# InkTime.net
KiCad netlist of a schematic drawn in EAGLE
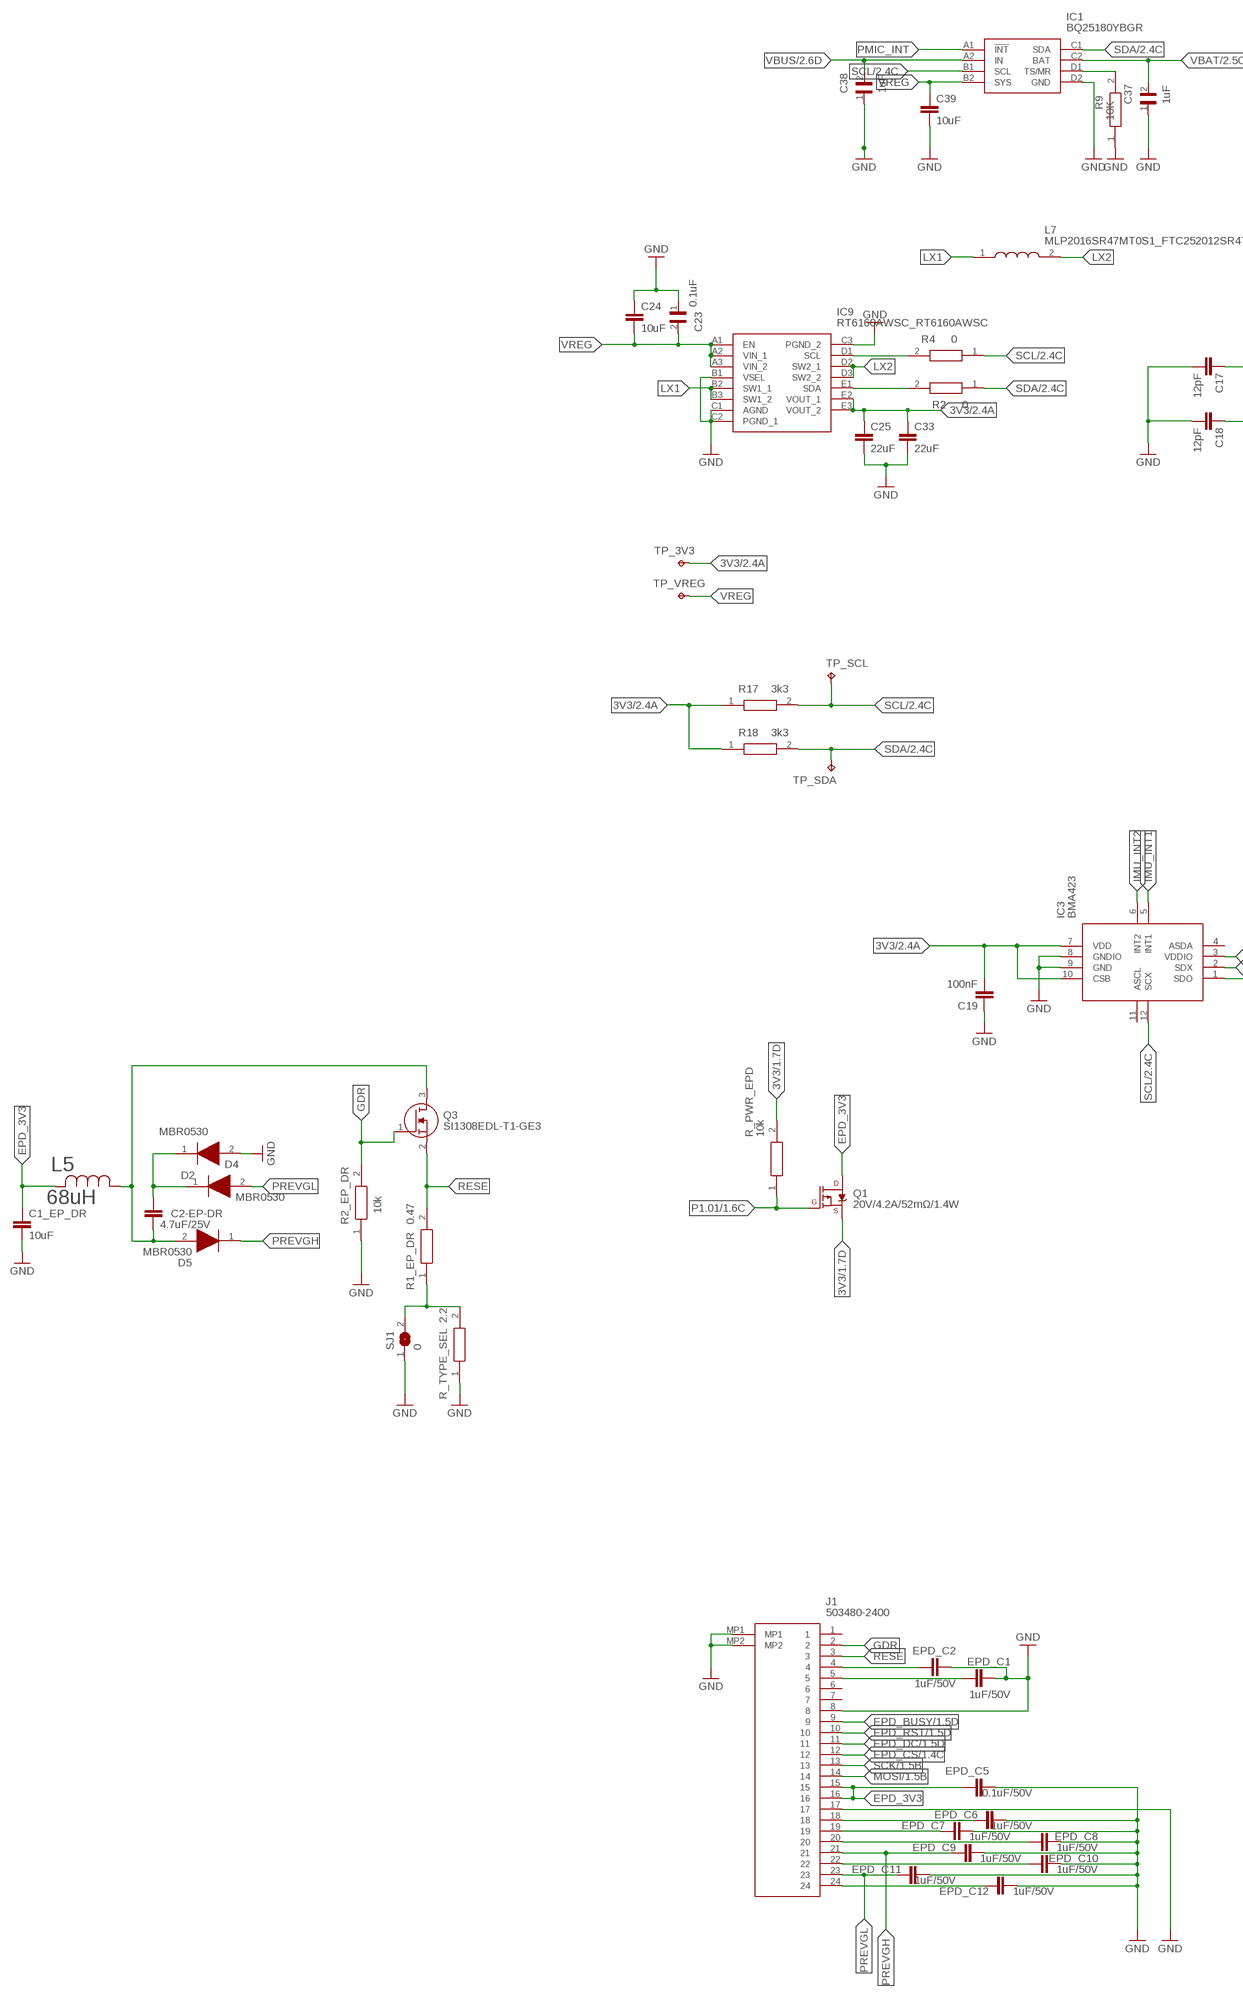
[diagram p0: schematic, sheet 1, part 1 of 2]
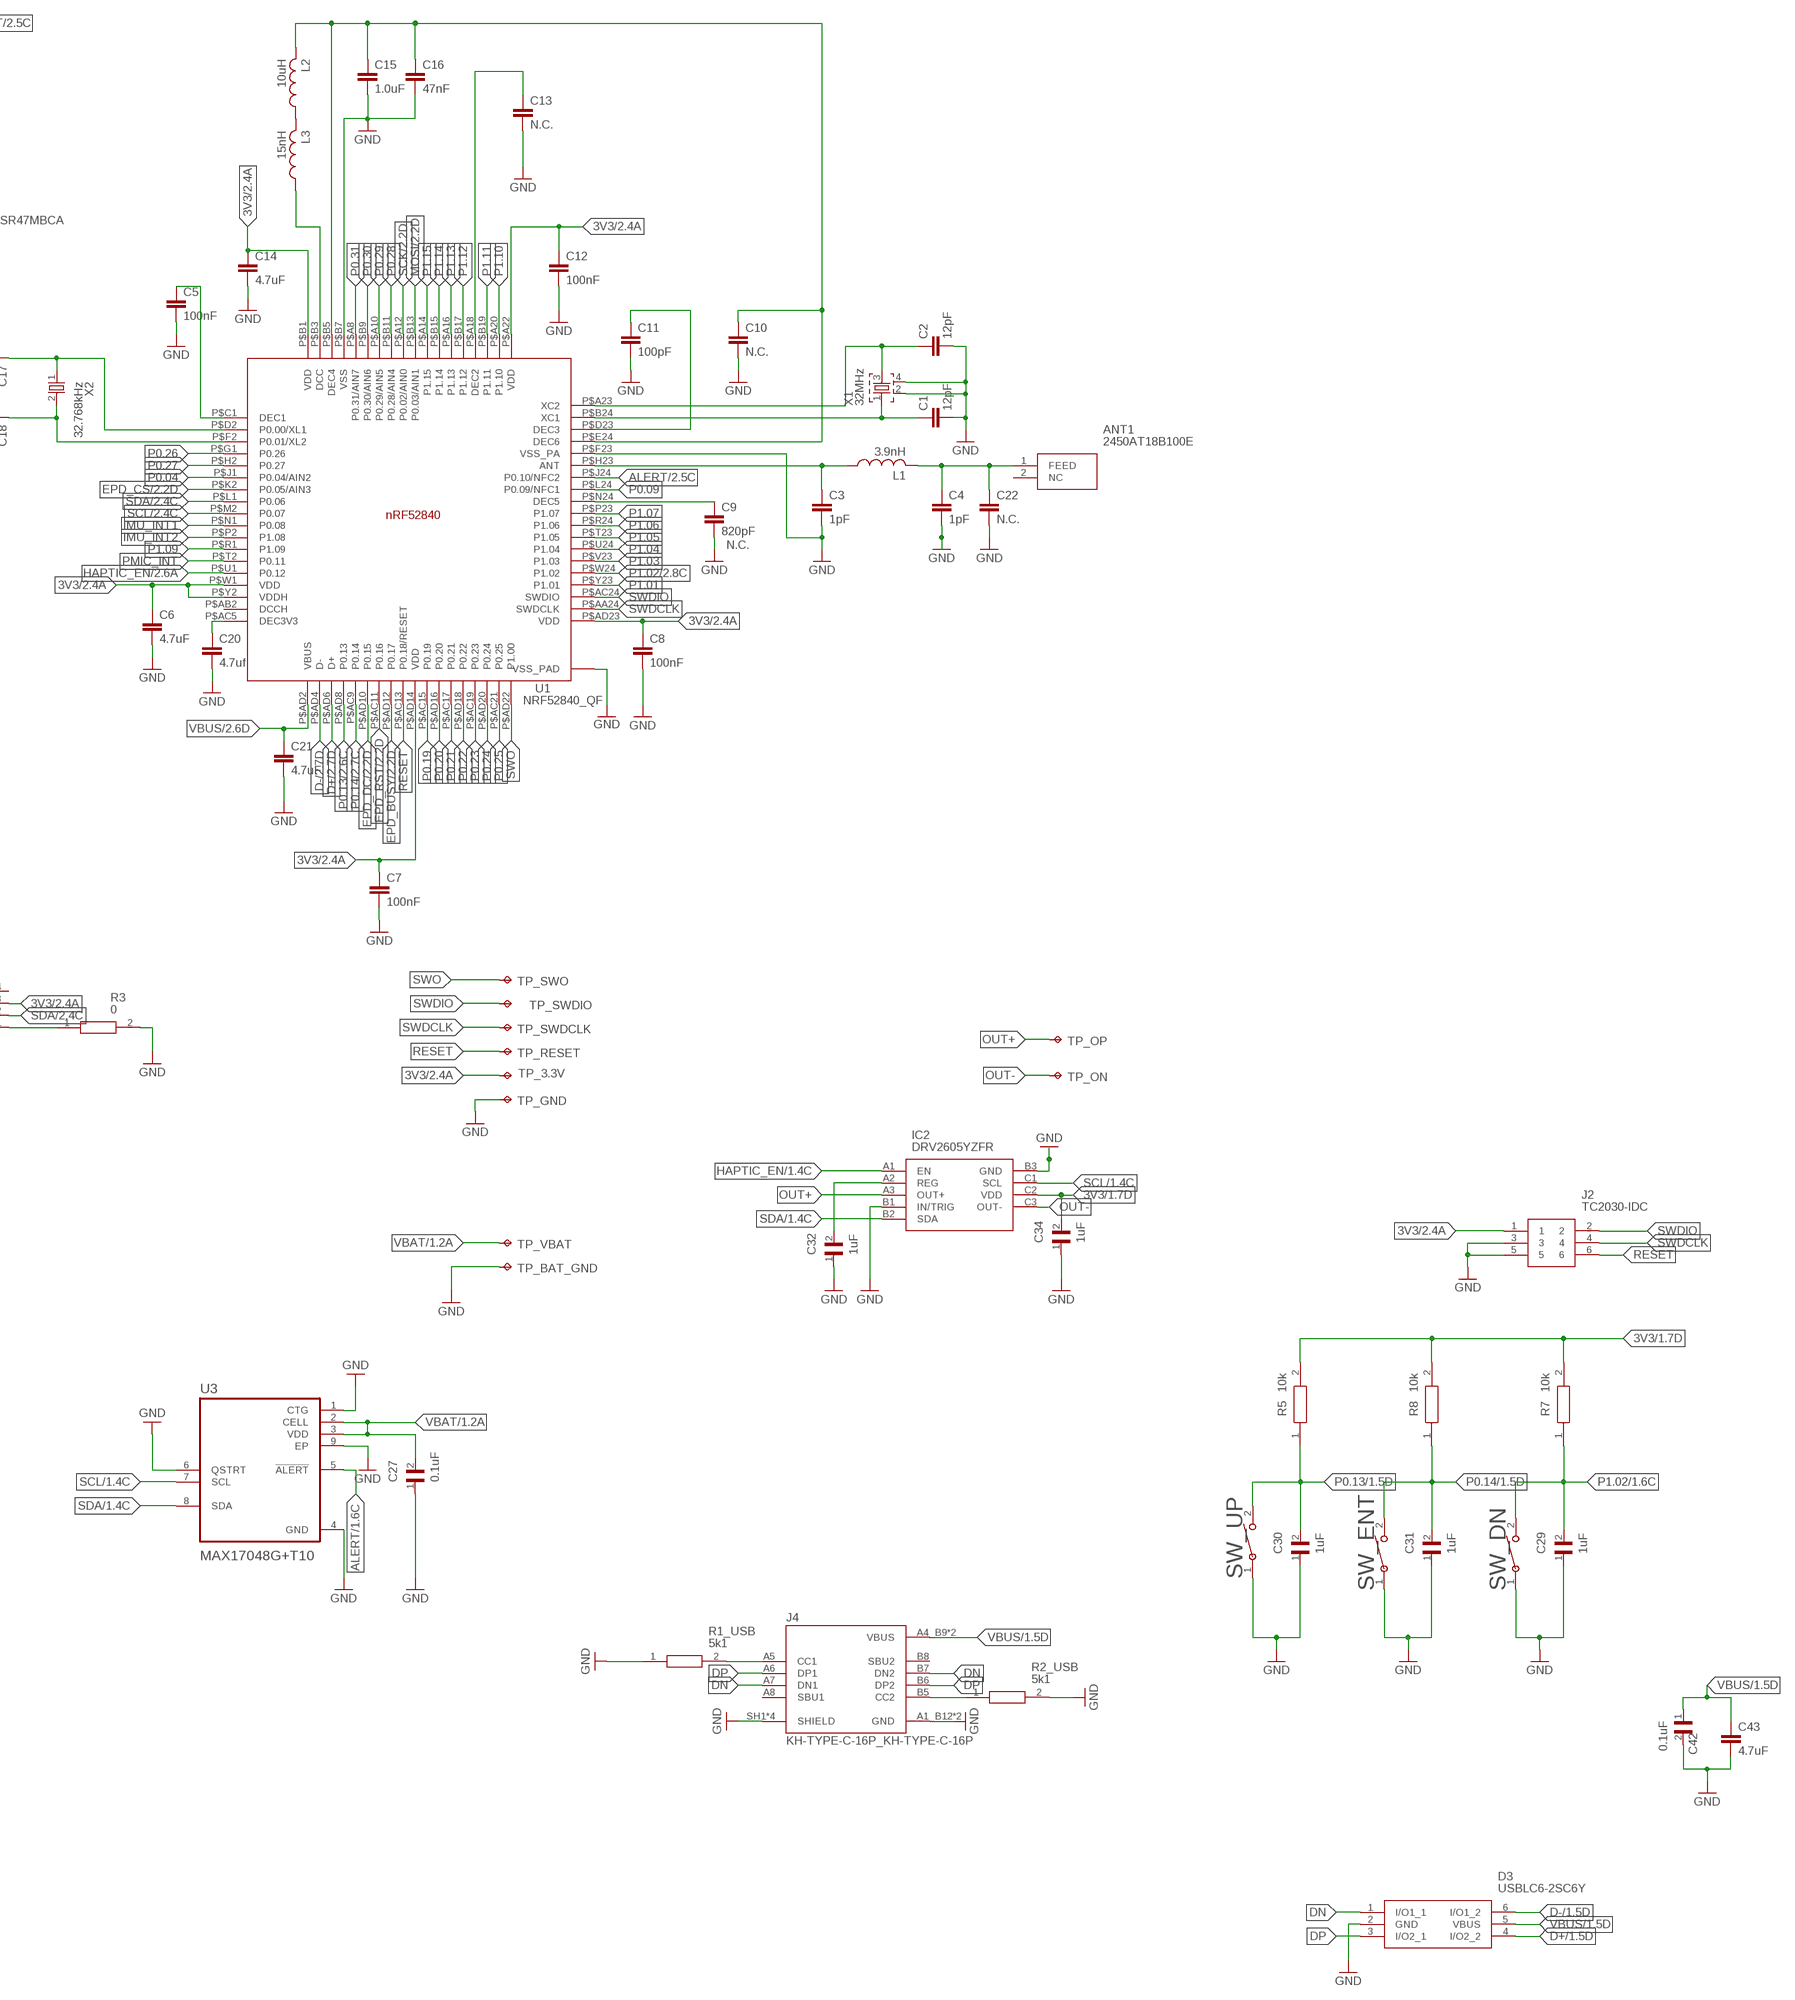
[diagram p1: schematic, sheet 1, part 2 of 2]

(export (version "E")
  (design (tool "Eeschema 10.0.6"))
  (components
    (comp (ref "ANT1")
      (value "2450AT18B100E")
      (footprint "eagle-import:2450AT18B100E_ANTC3216X140N")
      (fields (field (name "MOUSER_PART_NUMBER") "609-2450AT18B100E"))
      (libsource (lib "eagle-import") (part "2450AT18B100E_2450AT18B100E"))
    )
    (comp (ref "C1")
      (value "12pF")
      (footprint "eagle-import:NORDIC_NRF_3_RESC0201_L")
      (libsource (lib "eagle-import") (part "NORDIC_NRF_3_CAPACITOR_0201_L"))
    )
    (comp (ref "C1_EP_DR")
      (value "10uF")
      (footprint "eagle-import:NORDIC_NRF_3_RESC0402_L")
      (libsource (lib "eagle-import") (part "NORDIC_NRF_3_CAPACITOR_0402_L"))
    )
    (comp (ref "C2")
      (value "12pF")
      (footprint "eagle-import:NORDIC_NRF_3_RESC0201_L")
      (libsource (lib "eagle-import") (part "NORDIC_NRF_3_CAPACITOR_0201_L"))
    )
    (comp (ref "C2-EP-DR")
      (value "4.7uF/25V")
      (footprint "eagle-import:NORDIC_NRF_3_RESC0603_L")
      (libsource (lib "eagle-import") (part "NORDIC_NRF_3_CAPACITOR_0603_L"))
    )
    (comp (ref "C3")
      (value "1pF")
      (footprint "eagle-import:NORDIC_NRF_3_RESC0201_L")
      (libsource (lib "eagle-import") (part "NORDIC_NRF_3_CAPACITOR_0201_L"))
    )
    (comp (ref "C4")
      (value "1pF")
      (footprint "eagle-import:NORDIC_NRF_3_RESC0201_L")
      (libsource (lib "eagle-import") (part "NORDIC_NRF_3_CAPACITOR_0201_L"))
    )
    (comp (ref "C5")
      (value "100nF")
      (footprint "eagle-import:NORDIC_NRF_3_RESC0201_L")
      (libsource (lib "eagle-import") (part "NORDIC_NRF_3_CAPACITOR_0201_L"))
    )
    (comp (ref "C6")
      (value "4.7uF")
      (footprint "eagle-import:NORDIC_NRF_3_RESC0402_L")
      (libsource (lib "eagle-import") (part "NORDIC_NRF_3_CAPACITOR_0402_L"))
    )
    (comp (ref "C7")
      (value "100nF")
      (footprint "eagle-import:NORDIC_NRF_3_RESC0201_L")
      (libsource (lib "eagle-import") (part "NORDIC_NRF_3_CAPACITOR_0201_L"))
    )
    (comp (ref "C8")
      (value "100nF")
      (footprint "eagle-import:NORDIC_NRF_3_RESC0201_L")
      (libsource (lib "eagle-import") (part "NORDIC_NRF_3_CAPACITOR_0201_L"))
    )
    (comp (ref "C9")
      (value "820pF")
      (footprint "eagle-import:NORDIC_NRF_3_RESC0201_L")
      (fields (field (name "STATUS") "N.C."))
      (libsource (lib "eagle-import") (part "NORDIC_NRF_3_CAPACITOR_0201_L"))
    )
    (comp (ref "C10")
      (value "N.C.")
      (footprint "eagle-import:NORDIC_NRF_3_RESC0402_L")
      (libsource (lib "eagle-import") (part "NORDIC_NRF_3_CAPACITOR_0402_L"))
    )
    (comp (ref "C11")
      (value "100pF")
      (footprint "eagle-import:NORDIC_NRF_3_RESC0201_L")
      (libsource (lib "eagle-import") (part "NORDIC_NRF_3_CAPACITOR_0201_L"))
    )
    (comp (ref "C12")
      (value "100nF")
      (footprint "eagle-import:NORDIC_NRF_3_RESC0201_L")
      (libsource (lib "eagle-import") (part "NORDIC_NRF_3_CAPACITOR_0201_L"))
    )
    (comp (ref "C13")
      (value "N.C.")
      (footprint "eagle-import:NORDIC_NRF_3_RESC0402_L")
      (libsource (lib "eagle-import") (part "NORDIC_NRF_3_CAPACITOR_0402_L"))
    )
    (comp (ref "C14")
      (value "4.7uF")
      (footprint "eagle-import:NORDIC_NRF_3_RESC0402_L")
      (libsource (lib "eagle-import") (part "NORDIC_NRF_3_CAPACITOR_0402_L"))
    )
    (comp (ref "C15")
      (value "1.0uF")
      (footprint "eagle-import:NORDIC_NRF_3_RESC0402_L")
      (libsource (lib "eagle-import") (part "NORDIC_NRF_3_CAPACITOR_0402_L"))
    )
    (comp (ref "C16")
      (value "47nF")
      (footprint "eagle-import:NORDIC_NRF_3_RESC0201_L")
      (libsource (lib "eagle-import") (part "NORDIC_NRF_3_CAPACITOR_0201_L"))
    )
    (comp (ref "C17")
      (value "12pF")
      (footprint "eagle-import:NORDIC_NRF_3_RESC0201_L")
      (libsource (lib "eagle-import") (part "NORDIC_NRF_3_CAPACITOR_0201_L"))
    )
    (comp (ref "C18")
      (value "12pF")
      (footprint "eagle-import:NORDIC_NRF_3_RESC0201_L")
      (libsource (lib "eagle-import") (part "NORDIC_NRF_3_CAPACITOR_0201_L"))
    )
    (comp (ref "C19")
      (value "100nF")
      (footprint "eagle-import:NORDIC_NRF_3_RESC0201_L")
      (libsource (lib "eagle-import") (part "NORDIC_NRF_3_CAPACITOR_0201_L"))
    )
    (comp (ref "C20")
      (value "4.7uf")
      (footprint "eagle-import:NORDIC_NRF_3_RESC0201_L")
      (libsource (lib "eagle-import") (part "NORDIC_NRF_3_CAPACITOR_0201_L"))
    )
    (comp (ref "C21")
      (value "4.7uF")
      (footprint "eagle-import:NORDIC_NRF_3_RESC0402_L")
      (libsource (lib "eagle-import") (part "NORDIC_NRF_3_CAPACITOR_0402_L"))
    )
    (comp (ref "C22")
      (value "N.C.")
      (footprint "eagle-import:NORDIC_NRF_3_RESC0402_L")
      (libsource (lib "eagle-import") (part "NORDIC_NRF_3_CAPACITOR_0402_L"))
    )
    (comp (ref "C23")
      (value "0.1uF")
      (footprint "eagle-import:GRM011R60J152KE01L_2_CAPC0201X13N")
      (fields (field (name "MF") "Murata") (field (name "MP") "GRM011R60J152KE01L"))
      (libsource (lib "eagle-import") (part "GRM011R60J152KE01L_2_GRM011R60J152KE01L"))
    )
    (comp (ref "C24")
      (value "10uF")
      (footprint "eagle-import:NORDIC_NRF_3_RESC0402_L")
      (libsource (lib "eagle-import") (part "NORDIC_NRF_3_CAPACITOR_0402_L"))
    )
    (comp (ref "C25")
      (value "22uF")
      (footprint "eagle-import:NORDIC_NRF_3_RESC0402_L")
      (libsource (lib "eagle-import") (part "NORDIC_NRF_3_CAPACITOR_0402_L"))
    )
    (comp (ref "C27")
      (value "0.1uF")
      (footprint "eagle-import:GRM011R60J152KE01L_2_CAPC0201X13N")
      (fields (field (name "MF") "Murata") (field (name "MP") "GRM011R60J152KE01L"))
      (libsource (lib "eagle-import") (part "GRM011R60J152KE01L_2_GRM011R60J152KE01L"))
    )
    (comp (ref "C29")
      (value "1uF")
      (footprint "eagle-import:GRM011R60J152KE01L_2_CAPC0201X13N")
      (fields (field (name "MF") "Murata") (field (name "MP") "GRM011R60J152KE01L"))
      (libsource (lib "eagle-import") (part "GRM011R60J152KE01L_2_GRM011R60J152KE01L"))
    )
    (comp (ref "C30")
      (value "1uF")
      (footprint "eagle-import:GRM011R60J152KE01L_2_CAPC0201X13N")
      (fields (field (name "MF") "Murata") (field (name "MP") "GRM011R60J152KE01L"))
      (libsource (lib "eagle-import") (part "GRM011R60J152KE01L_2_GRM011R60J152KE01L"))
    )
    (comp (ref "C31")
      (value "1uF")
      (footprint "eagle-import:GRM011R60J152KE01L_2_CAPC0201X13N")
      (fields (field (name "MF") "Murata") (field (name "MP") "GRM011R60J152KE01L"))
      (libsource (lib "eagle-import") (part "GRM011R60J152KE01L_2_GRM011R60J152KE01L"))
    )
    (comp (ref "C32")
      (value "1uF")
      (footprint "eagle-import:GRM011R60J152KE01L_2_CAPC0201X13N")
      (fields (field (name "MF") "Murata") (field (name "MP") "GRM011R60J152KE01L"))
      (libsource (lib "eagle-import") (part "GRM011R60J152KE01L_2_GRM011R60J152KE01L"))
    )
    (comp (ref "C33")
      (value "22uF")
      (footprint "eagle-import:NORDIC_NRF_3_RESC0402_L")
      (libsource (lib "eagle-import") (part "NORDIC_NRF_3_CAPACITOR_0402_L"))
    )
    (comp (ref "C34")
      (value "1uF")
      (footprint "eagle-import:GRM011R60J152KE01L_2_CAPC0201X13N")
      (fields (field (name "MF") "Murata") (field (name "MP") "GRM011R60J152KE01L"))
      (libsource (lib "eagle-import") (part "GRM011R60J152KE01L_2_GRM011R60J152KE01L"))
    )
    (comp (ref "C37")
      (value "1uF")
      (footprint "eagle-import:GRM011R60J152KE01L_2_CAPC0201X13N")
      (fields (field (name "MF") "Murata") (field (name "MP") "GRM011R60J152KE01L"))
      (libsource (lib "eagle-import") (part "GRM011R60J152KE01L_2_GRM011R60J152KE01L"))
    )
    (comp (ref "C38")
      (value "1uF")
      (footprint "eagle-import:GRM011R60J152KE01L_2_CAPC0201X13N")
      (fields (field (name "MF") "Murata") (field (name "MP") "GRM011R60J152KE01L"))
      (libsource (lib "eagle-import") (part "GRM011R60J152KE01L_2_GRM011R60J152KE01L"))
    )
    (comp (ref "C39")
      (value "10uF")
      (footprint "eagle-import:NORDIC_NRF_3_RESC0402_L")
      (libsource (lib "eagle-import") (part "NORDIC_NRF_3_CAPACITOR_0402_L"))
    )
    (comp (ref "C42")
      (value "0.1uF")
      (footprint "eagle-import:GRM011R60J152KE01L_2_CAPC0201X13N")
      (fields (field (name "MF") "Murata") (field (name "MP") "GRM011R60J152KE01L"))
      (libsource (lib "eagle-import") (part "GRM011R60J152KE01L_2_GRM011R60J152KE01L"))
    )
    (comp (ref "C43")
      (value "4.7uF")
      (footprint "eagle-import:NORDIC_NRF_3_RESC0402_L")
      (libsource (lib "eagle-import") (part "NORDIC_NRF_3_CAPACITOR_0402_L"))
    )
    (comp (ref "D2")
      (value "MBR0530")
      (footprint "eagle-import:ESP32_C6_LIBRARY_5_SOD3716X135N")
      (fields (field (name "MF") "ON Semiconductor"))
      (libsource (lib "eagle-import") (part "ESP32_C6_LIBRARY_5_MBR0530"))
    )
    (comp (ref "D3")
      (value "USBLC6-2SC6Y")
      (footprint "eagle-import:ESP32_C6_LIBRARY_3_SOT95P280X145-6N")
      (fields (field (name "MF") "STMicroelectronics"))
      (libsource (lib "eagle-import") (part "ESP32_C6_LIBRARY_3_USBLC6-2SC6Y"))
    )
    (comp (ref "D4")
      (value "MBR0530")
      (footprint "eagle-import:ESP32_C6_LIBRARY_5_SOD3716X135N")
      (fields (field (name "MF") "ON Semiconductor"))
      (libsource (lib "eagle-import") (part "ESP32_C6_LIBRARY_5_MBR0530"))
    )
    (comp (ref "D5")
      (value "MBR0530")
      (footprint "eagle-import:ESP32_C6_LIBRARY_5_SOD3716X135N")
      (fields (field (name "MF") "ON Semiconductor"))
      (libsource (lib "eagle-import") (part "ESP32_C6_LIBRARY_5_MBR0530"))
    )
    (comp (ref "EPD_C1")
      (value "1uF/50V")
      (footprint "eagle-import:RESC0402_L")
      (libsource (lib "eagle-import") (part "CAPACITOR_0402_L"))
    )
    (comp (ref "EPD_C2")
      (value "1uF/50V")
      (footprint "eagle-import:RESC0402_L")
      (libsource (lib "eagle-import") (part "CAPACITOR_0402_L"))
    )
    (comp (ref "EPD_C5")
      (value "0.1uF/50V")
      (footprint "eagle-import:RESC0402_L")
      (libsource (lib "eagle-import") (part "CAPACITOR_0402_L"))
    )
    (comp (ref "EPD_C6")
      (value "1uF/50V")
      (footprint "eagle-import:RESC0402_L")
      (libsource (lib "eagle-import") (part "CAPACITOR_0402_L"))
    )
    (comp (ref "EPD_C7")
      (value "1uF/50V")
      (footprint "eagle-import:RESC0402_L")
      (libsource (lib "eagle-import") (part "CAPACITOR_0402_L"))
    )
    (comp (ref "EPD_C8")
      (value "1uF/50V")
      (footprint "eagle-import:RESC0402_L")
      (libsource (lib "eagle-import") (part "CAPACITOR_0402_L"))
    )
    (comp (ref "EPD_C9")
      (value "1uF/50V")
      (footprint "eagle-import:RESC0402_L")
      (libsource (lib "eagle-import") (part "CAPACITOR_0402_L"))
    )
    (comp (ref "EPD_C10")
      (value "1uF/50V")
      (footprint "eagle-import:RESC0402_L")
      (libsource (lib "eagle-import") (part "CAPACITOR_0402_L"))
    )
    (comp (ref "EPD_C11")
      (value "1uF/50V")
      (footprint "eagle-import:RESC0402_L")
      (libsource (lib "eagle-import") (part "CAPACITOR_0402_L"))
    )
    (comp (ref "EPD_C12")
      (value "1uF/50V")
      (footprint "eagle-import:RESC0402_L")
      (libsource (lib "eagle-import") (part "CAPACITOR_0402_L"))
    )
    (comp (ref "IC1")
      (value "BQ25180YBGR")
      (footprint "eagle-import:BQ25180YBGR_BGA8C40P2X4_100X155X50")
      (fields (field (name "MOUSER_PART_NUMBER") "595-BQ25180YBGR"))
      (libsource (lib "eagle-import") (part "BQ25180YBGR_BQ25180YBGR"))
    )
    (comp (ref "IC2")
      (value "DRV2605YZFR")
      (footprint "eagle-import:DRV2605YZFR_BGA9C50P3X3_144X144X62")
      (libsource (lib "eagle-import") (part "DRV2605YZFR_DRV2605YZFR"))
    )
    (comp (ref "IC3")
      (value "BMA423")
      (footprint "eagle-import:BMA423_BMA423")
      (fields (field (name "MOUSER_PART_NUMBER") "262-BMA423"))
      (libsource (lib "eagle-import") (part "BMA423_BMA423"))
    )
    (comp (ref "IC9")
      (value "RT6160AWSC_RT6160AWSC")
      (footprint "eagle-import:RT6160AWSC_BGA15C40P3X5_140X230X60")
      (fields
        (field (name "MANUFACTURER_PART_NUMBER") "RT6160AWSC")
        (field (name "MOUSER_PART_NUMBER") "835-RT6160AWSC")
      )
      (libsource (lib "eagle-import") (part "RT6160AWSC_RT6160AWSC"))
    )
    (comp (ref "J1")
      (value "503480-2400")
      (footprint "eagle-import:503480-2400_5034802400")
      (fields (field (name "MOUSER_PART_NUMBER") "538-503480-2400"))
      (libsource (lib "eagle-import") (part "503480-2400_503480-2400"))
    )
    (comp (ref "J2")
      (value "TC2030-IDC")
      (footprint "eagle-import:TC2030-IDC_TC2030IDC")
      (libsource (lib "eagle-import") (part "TC2030-IDC_TC2030-IDC"))
    )
    (comp (ref "J4")
      (value "KH-TYPE-C-16P_KH-TYPE-C-16P")
      (footprint "eagle-import:KH-TYPE-C-16P_KINGHELM_KH-TYPE-C-16P")
      (fields (field (name "MF") "kinghelm") (field (name "MP") "KH-TYPE-C-16P"))
      (libsource (lib "eagle-import") (part "KH-TYPE-C-16P_KH-TYPE-C-16P"))
    )
    (comp (ref "L1")
      (value "3.9nH")
      (footprint "eagle-import:NORDIC_NRF_2_RESC0402_L")
      (libsource (lib "eagle-import") (part "NORDIC_NRF_2_INDUCTOR_0402_L"))
    )
    (comp (ref "L2")
      (value "10uH")
      (footprint "eagle-import:NORDIC_NRF_2_RESC0603_L")
      (libsource (lib "eagle-import") (part "NORDIC_NRF_2_INDUCTOR_0603_L"))
    )
    (comp (ref "L3")
      (value "15nH")
      (footprint "eagle-import:NORDIC_NRF_2_RESC0402_L")
      (libsource (lib "eagle-import") (part "NORDIC_NRF_2_INDUCTOR_0402_L"))
    )
    (comp (ref "L5")
      (value "68uH")
      (footprint "eagle-import:ESP32_C6_LIBRARY_2_IND_4828-WE-TPC_WRE")
      (fields
        (field (name "MANUFACTURER_PART_NUMBER") "744043680")
        (field (name "COPYRIGHT") "Copyright (C) 2024 Ultra Librarian. All rights reserved.")
      )
      (libsource (lib "eagle-import") (part "ESP32_C6_LIBRARY_2_744043680IND_4828-WE-TPC_WRE"))
    )
    (comp (ref "L7")
      (value "MLP2016SR47MT0S1_FTC252012SR47MBCA")
      (footprint "eagle-import:MLP2016SR47MT0S1_INDC2016X100N")
      (fields (field (name "MANUFACTURER_PART_NUMBER") "FTC252012SR47MBCA"))
      (libsource (lib "eagle-import") (part "MLP2016SR47MT0S1_FTC252012SR47MBCA"))
    )
    (comp (ref "Q1")
      (value "20V/4.2A/52mΩ/1.4W")
      (footprint "eagle-import:ESP32_C6_LIBRARY_4_ESP32_C6_LIBRARY_4_ESP32_C6_LIBRARY_4_ESP32_C6_LIBRARY_4_ESP32_WROVER_SPARKFUN-DISCRETESEMI_SOT23-3")
      (libsource (lib "eagle-import") (part "ESP32_C6_LIBRARY_4_ESP32_WROVER_SPARKFUN-DISCRETESEMI_MOSFET_PCH-DMG2305UX-7"))
    )
    (comp (ref "Q3")
      (value "SI1308EDL-T1-GE3")
      (footprint "eagle-import:ESP32_C6_LIBRARY_6_SOT65P210X110-3N")
      (fields (field (name "MF") "Vishay Siliconix"))
      (libsource (lib "eagle-import") (part "ESP32_C6_LIBRARY_6_SI1308EDL-T1-GE3"))
    )
    (comp (ref "R1_EP_DR")
      (value "0.47")
      (footprint "eagle-import:ERA-1AEB3401C_0201")
      (libsource (lib "eagle-import") (part "ERA-1AEB3401C_CPF0201D7K68C1"))
    )
    (comp (ref "R1_USB")
      (value "5k1")
      (footprint "eagle-import:ERA-1AEB3401C_0201")
      (libsource (lib "eagle-import") (part "ERA-1AEB3401C_CPF0201D7K68C1"))
    )
    (comp (ref "R2")
      (value "0")
      (footprint "eagle-import:ERA-1AEB3401C_0201")
      (libsource (lib "eagle-import") (part "ERA-1AEB3401C_CPF0201D7K68C1"))
    )
    (comp (ref "R2_EP_DR")
      (value "10k")
      (footprint "eagle-import:ERA-1AEB3401C_0201")
      (libsource (lib "eagle-import") (part "ERA-1AEB3401C_CPF0201D7K68C1"))
    )
    (comp (ref "R2_USB")
      (value "5k1")
      (footprint "eagle-import:ERA-1AEB3401C_0201")
      (libsource (lib "eagle-import") (part "ERA-1AEB3401C_CPF0201D7K68C1"))
    )
    (comp (ref "R3")
      (value "0")
      (footprint "eagle-import:ERA-1AEB3401C_0201")
      (libsource (lib "eagle-import") (part "ERA-1AEB3401C_CPF0201D7K68C1"))
    )
    (comp (ref "R4")
      (value "0")
      (footprint "eagle-import:ERA-1AEB3401C_0201")
      (libsource (lib "eagle-import") (part "ERA-1AEB3401C_CPF0201D7K68C1"))
    )
    (comp (ref "R5")
      (value "10k")
      (footprint "eagle-import:ERA-1AEB3401C_0201")
      (libsource (lib "eagle-import") (part "ERA-1AEB3401C_CPF0201D7K68C1"))
    )
    (comp (ref "R7")
      (value "10k")
      (footprint "eagle-import:ERA-1AEB3401C_0201")
      (libsource (lib "eagle-import") (part "ERA-1AEB3401C_CPF0201D7K68C1"))
    )
    (comp (ref "R8")
      (value "10k")
      (footprint "eagle-import:ERA-1AEB3401C_0201")
      (libsource (lib "eagle-import") (part "ERA-1AEB3401C_CPF0201D7K68C1"))
    )
    (comp (ref "R9")
      (value "10K")
      (footprint "eagle-import:CPF0201D7K68C1_0201")
      (libsource (lib "eagle-import") (part "CPF0201D7K68C1_CPF0201D7K68C1"))
    )
    (comp (ref "R17")
      (value "3k3")
      (footprint "eagle-import:ERA-1AEB3401C_0201")
      (libsource (lib "eagle-import") (part "ERA-1AEB3401C_CPF0201D7K68C1"))
    )
    (comp (ref "R18")
      (value "3k3")
      (footprint "eagle-import:CPF0201D7K68C1_0201")
      (libsource (lib "eagle-import") (part "CPF0201D7K68C1_CPF0201D7K68C1"))
    )
    (comp (ref "R_PWR_EPD")
      (value "10k")
      (footprint "eagle-import:ERA-1AEB3401C_0201")
      (libsource (lib "eagle-import") (part "ERA-1AEB3401C_CPF0201D7K68C1"))
    )
    (comp (ref "R_TYPE_SEL")
      (value "2.2")
      (footprint "eagle-import:ERA-1AEB3401C_0201")
      (libsource (lib "eagle-import") (part "ERA-1AEB3401C_CPF0201D7K68C1"))
    )
    (comp (ref "SJ1")
      (value "0")
      (footprint "eagle-import:ESP32_C6_LIBRARY_7_JUMPER_SJ")
      (libsource (lib "eagle-import") (part "ESP32_C6_LIBRARY_7_JUMPER_SJ"))
    )
    (comp (ref "SW_DN")
      (value "2025-10-22_07-23-44_LIBRARY_EVP-AKE31ASW_EVP-AKE31A_PAN")
      (footprint "eagle-import:2025-10-22_07-23-44_LIBRARY_SW_EVP-AKE31A_PAN")
      (fields
        (field (name "MANUFACTURER_PART_NUMBER") "EVP-AKE31A")
        (field (name "COPYRIGHT") "Copyright (C) 2025 Ultra Librarian. All rights reserved.")
      )
      (libsource (lib "eagle-import") (part "2025-10-22_07-23-44_LIBRARY_EVP-AKE31ASW_EVP-AKE31A_PAN"))
    )
    (comp (ref "SW_ENT")
      (value "2025-10-22_07-23-44_LIBRARY_EVP-AKE31ASW_EVP-AKE31A_PAN")
      (footprint "eagle-import:2025-10-22_07-23-44_LIBRARY_SW_EVP-AKE31A_PAN")
      (fields
        (field (name "MANUFACTURER_PART_NUMBER") "EVP-AKE31A")
        (field (name "COPYRIGHT") "Copyright (C) 2025 Ultra Librarian. All rights reserved.")
      )
      (libsource (lib "eagle-import") (part "2025-10-22_07-23-44_LIBRARY_EVP-AKE31ASW_EVP-AKE31A_PAN"))
    )
    (comp (ref "SW_UP")
      (value "2025-10-22_07-23-44_LIBRARY_EVP-AKE31ASW_EVP-AKE31A_PAN")
      (footprint "eagle-import:2025-10-22_07-23-44_LIBRARY_SW_EVP-AKE31A_PAN")
      (fields
        (field (name "MANUFACTURER_PART_NUMBER") "EVP-AKE31A")
        (field (name "COPYRIGHT") "Copyright (C) 2025 Ultra Librarian. All rights reserved.")
      )
      (libsource (lib "eagle-import") (part "2025-10-22_07-23-44_LIBRARY_EVP-AKE31ASW_EVP-AKE31A_PAN"))
    )
    (comp (ref "TP_3.3V")
      (value "HECTOR_WATCH_1_TPTP20R")
      (footprint "eagle-import:HECTOR_WATCH_1_TP20R")
      (libsource (lib "eagle-import") (part "HECTOR_WATCH_1_TPTP20R"))
    )
    (comp (ref "TP_3V3")
      (value "HECTOR_WATCH_1_TPTP20R")
      (footprint "eagle-import:HECTOR_WATCH_1_TP20R")
      (libsource (lib "eagle-import") (part "HECTOR_WATCH_1_TPTP20R"))
    )
    (comp (ref "TP_BAT_GND")
      (value "HECTOR_WATCH_1_TPTP20R")
      (footprint "eagle-import:HECTOR_WATCH_1_TP20R")
      (libsource (lib "eagle-import") (part "HECTOR_WATCH_1_TPTP20R"))
    )
    (comp (ref "TP_GND")
      (value "HECTOR_WATCH_1_TPTP20R")
      (footprint "eagle-import:HECTOR_WATCH_1_TP20R")
      (libsource (lib "eagle-import") (part "HECTOR_WATCH_1_TPTP20R"))
    )
    (comp (ref "TP_ON")
      (value "HECTOR_WATCH_1_TPTP20R")
      (footprint "eagle-import:HECTOR_WATCH_1_TP20R")
      (libsource (lib "eagle-import") (part "HECTOR_WATCH_1_TPTP20R"))
    )
    (comp (ref "TP_OP")
      (value "HECTOR_WATCH_1_TPTP20R")
      (footprint "eagle-import:HECTOR_WATCH_1_TP20R")
      (libsource (lib "eagle-import") (part "HECTOR_WATCH_1_TPTP20R"))
    )
    (comp (ref "TP_RESET")
      (value "HECTOR_WATCH_1_TPTP20R")
      (footprint "eagle-import:HECTOR_WATCH_1_TP20R")
      (libsource (lib "eagle-import") (part "HECTOR_WATCH_1_TPTP20R"))
    )
    (comp (ref "TP_SCL")
      (value "HECTOR_WATCH_1_TPTP20R")
      (footprint "eagle-import:HECTOR_WATCH_1_TP20R")
      (libsource (lib "eagle-import") (part "HECTOR_WATCH_1_TPTP20R"))
    )
    (comp (ref "TP_SDA")
      (value "HECTOR_WATCH_1_TPTP20R")
      (footprint "eagle-import:HECTOR_WATCH_1_TP20R")
      (libsource (lib "eagle-import") (part "HECTOR_WATCH_1_TPTP20R"))
    )
    (comp (ref "TP_SWDCLK")
      (value "HECTOR_WATCH_1_TPTP20R")
      (footprint "eagle-import:HECTOR_WATCH_1_TP20R")
      (libsource (lib "eagle-import") (part "HECTOR_WATCH_1_TPTP20R"))
    )
    (comp (ref "TP_SWDIO")
      (value "HECTOR_WATCH_1_TPTP20R")
      (footprint "eagle-import:HECTOR_WATCH_1_TP20R")
      (libsource (lib "eagle-import") (part "HECTOR_WATCH_1_TPTP20R"))
    )
    (comp (ref "TP_SWO")
      (value "HECTOR_WATCH_1_TPTP20R")
      (footprint "eagle-import:HECTOR_WATCH_1_TP20R")
      (libsource (lib "eagle-import") (part "HECTOR_WATCH_1_TPTP20R"))
    )
    (comp (ref "TP_VBAT")
      (value "HECTOR_WATCH_1_TPTP20R")
      (footprint "eagle-import:HECTOR_WATCH_1_TP20R")
      (libsource (lib "eagle-import") (part "HECTOR_WATCH_1_TPTP20R"))
    )
    (comp (ref "TP_VREG")
      (value "HECTOR_WATCH_1_TPTP20R")
      (footprint "eagle-import:HECTOR_WATCH_1_TP20R")
      (libsource (lib "eagle-import") (part "HECTOR_WATCH_1_TPTP20R"))
    )
    (comp (ref "U1")
      (value "NRF52840_QF")
      (footprint "eagle-import:NORDIC_NRF_4_AQFN50P700X700X85_HS-74N")
      (libsource (lib "eagle-import") (part "NORDIC_NRF_4_NRF52840_QF"))
    )
    (comp (ref "U3")
      (value "MAX17048G+T10")
      (footprint "eagle-import:ESP32_C6_LIBRARY_SON50P200X200X80-9N")
      (fields (field (name "MF") "Analog Devices"))
      (libsource (lib "eagle-import") (part "ESP32_C6_LIBRARY_MAX17048G+T10"))
    )
    (comp (ref "X1")
      (value "32MHz")
      (footprint "eagle-import:NORDIC_NRF_BT-XTAL_2016_N")
      (libsource (lib "eagle-import") (part "NORDIC_NRF_XTAL_32MHZ"))
    )
    (comp (ref "X2")
      (value "32.768kHz")
      (footprint "eagle-import:NORDIC_NRF_1_XTAL_3215_N")
      (libsource (lib "eagle-import") (part "NORDIC_NRF_1_XTAL_32KHZ"))
    )
  )
  (nets
    (net (code "1") (name "3V3{slash}1.7D") (class "Default")
      (node (ref "C34") (pin "2") (pinfunction "2_2") (pintype "passive"))
      (node (ref "IC2") (pin "C2") (pinfunction "VDD_C2") (pintype "bidirectional"))
      (node (ref "Q1") (pin "2") (pinfunction "S_2") (pintype "bidirectional"))
      (node (ref "R5") (pin "2") (pinfunction "2_2") (pintype "bidirectional"))
      (node (ref "R7") (pin "2") (pinfunction "2_2") (pintype "bidirectional"))
      (node (ref "R8") (pin "2") (pinfunction "2_2") (pintype "bidirectional"))
      (node (ref "R_PWR_EPD") (pin "2") (pinfunction "2_2") (pintype "bidirectional"))
    )
    (net (code "2") (name "3V3{slash}2.4A") (class "Default")
      (node (ref "C12") (pin "1") (pinfunction "1_1") (pintype "passive"))
      (node (ref "C14") (pin "1") (pinfunction "1_1") (pintype "passive"))
      (node (ref "C19") (pin "2") (pinfunction "2_2") (pintype "passive"))
      (node (ref "C25") (pin "1") (pinfunction "1_1") (pintype "passive"))
      (node (ref "C33") (pin "1") (pinfunction "1_1") (pintype "passive"))
      (node (ref "C6") (pin "1") (pinfunction "1_1") (pintype "passive"))
      (node (ref "C7") (pin "1") (pinfunction "1_1") (pintype "passive"))
      (node (ref "C8") (pin "1") (pinfunction "1_1") (pintype "passive"))
      (node (ref "IC3") (pin "10") (pinfunction "CSB_10") (pintype "bidirectional"))
      (node (ref "IC3") (pin "3") (pinfunction "VDDIO_3") (pintype "bidirectional"))
      (node (ref "IC3") (pin "7") (pinfunction "VDD_7") (pintype "bidirectional"))
      (node (ref "IC9") (pin "E2") (pinfunction "VOUT_1_E2") (pintype "bidirectional"))
      (node (ref "IC9") (pin "E3") (pinfunction "VOUT_2_E3") (pintype "bidirectional"))
      (node (ref "J2") (pin "1") (pinfunction "1_1") (pintype "bidirectional"))
      (node (ref "R17") (pin "1") (pinfunction "1_1") (pintype "bidirectional"))
      (node (ref "R18") (pin "1") (pinfunction "1_1") (pintype "bidirectional"))
      (node (ref "TP_3.3V") (pin "TP") (pinfunction "TP_TP") (pintype "input"))
      (node (ref "TP_3V3") (pin "TP") (pinfunction "TP_TP") (pintype "input"))
      (node (ref "U1") (pin "P$A22") (pinfunction "VDD_P$A22") (pintype "power_in"))
      (node (ref "U1") (pin "P$AD14") (pinfunction "VDD_P$AD14") (pintype "power_in"))
      (node (ref "U1") (pin "P$AD23") (pinfunction "VDD_P$AD23") (pintype "power_in"))
      (node (ref "U1") (pin "P$B1") (pinfunction "VDD_P$B1") (pintype "power_in"))
      (node (ref "U1") (pin "P$W1") (pinfunction "VDD_P$W1") (pintype "power_in"))
      (node (ref "U1") (pin "P$Y2") (pinfunction "VDDH_P$Y2") (pintype "power_in"))
    )
    (net (code "3") (name "ALERT{slash}1.6C") (class "Default")
      (node (ref "U3") (pin "5") (pinfunction "~{ALERT}_5") (pintype "output"))
    )
    (net (code "4") (name "ALERT{slash}2.5C") (class "Default")
      (node (ref "U1") (pin "P$J24") (pinfunction "P0.10/NFC2_P$J24") (pintype "bidirectional"))
    )
    (net (code "5") (name "D+{slash}1.5D") (class "Default")
      (node (ref "D3") (pin "4") (pinfunction "I/O2_2_4") (pintype "bidirectional"))
    )
    (net (code "6") (name "D+{slash}2.7D") (class "Default")
      (node (ref "U1") (pin "P$AD6") (pinfunction "D+_P$AD6") (pintype "bidirectional"))
    )
    (net (code "7") (name "D-{slash}1.5D") (class "Default")
      (node (ref "D3") (pin "6") (pinfunction "I/O1_2_6") (pintype "bidirectional"))
    )
    (net (code "8") (name "D-{slash}2.7D") (class "Default")
      (node (ref "U1") (pin "P$AD4") (pinfunction "D-_P$AD4") (pintype "bidirectional"))
    )
    (net (code "9") (name "DN") (class "Default")
      (node (ref "D3") (pin "1") (pinfunction "I/O1_1_1") (pintype "bidirectional"))
      (node (ref "J4") (pin "A7") (pinfunction "DN1_A7") (pintype "bidirectional"))
      (node (ref "J4") (pin "B7") (pinfunction "DN2_B7") (pintype "bidirectional"))
    )
    (net (code "10") (name "DP") (class "Default")
      (node (ref "D3") (pin "3") (pinfunction "I/O2_1_3") (pintype "bidirectional"))
      (node (ref "J4") (pin "A6") (pinfunction "DP1_A6") (pintype "bidirectional"))
      (node (ref "J4") (pin "B6") (pinfunction "DP2_B6") (pintype "bidirectional"))
    )
    (net (code "11") (name "EPD_3V3") (class "Default")
      (node (ref "C1_EP_DR") (pin "1") (pinfunction "1_1") (pintype "passive"))
      (node (ref "EPD_C5") (pin "1") (pinfunction "1_1") (pintype "passive"))
      (node (ref "J1") (pin "15") (pinfunction "15_15") (pintype "bidirectional"))
      (node (ref "J1") (pin "16") (pinfunction "16_16") (pintype "bidirectional"))
      (node (ref "L5") (pin "2") (pinfunction "2_2") (pintype "passive"))
      (node (ref "Q1") (pin "3") (pinfunction "D_3") (pintype "bidirectional"))
    )
    (net (code "12") (name "EPD_BUSY{slash}1.5D") (class "Default")
      (node (ref "J1") (pin "9") (pinfunction "9_9") (pintype "bidirectional"))
    )
    (net (code "13") (name "EPD_BUSY{slash}2.2D") (class "Default")
      (node (ref "U1") (pin "P$AD12") (pinfunction "P0.17_P$AD12") (pintype "bidirectional"))
    )
    (net (code "14") (name "EPD_CS{slash}1.4C") (class "Default")
      (node (ref "J1") (pin "12") (pinfunction "12_12") (pintype "bidirectional"))
    )
    (net (code "15") (name "EPD_CS{slash}2.2D") (class "Default")
      (node (ref "U1") (pin "P$K2") (pinfunction "P0.05/AIN3_P$K2") (pintype "bidirectional"))
    )
    (net (code "16") (name "EPD_DC{slash}1.5D") (class "Default")
      (node (ref "J1") (pin "11") (pinfunction "11_11") (pintype "bidirectional"))
    )
    (net (code "17") (name "EPD_DC{slash}2.2D") (class "Default")
      (node (ref "U1") (pin "P$AD10") (pinfunction "P0.15_P$AD10") (pintype "bidirectional"))
    )
    (net (code "18") (name "EPD_RST{slash}1.5D") (class "Default")
      (node (ref "J1") (pin "10") (pinfunction "10_10") (pintype "bidirectional"))
    )
    (net (code "19") (name "EPD_RST{slash}2.2D") (class "Default")
      (node (ref "U1") (pin "P$AC11") (pinfunction "P0.16_P$AC11") (pintype "bidirectional"))
    )
    (net (code "20") (name "GDR") (class "Default")
      (node (ref "J1") (pin "2") (pinfunction "2_2") (pintype "bidirectional"))
      (node (ref "Q3") (pin "1") (pinfunction "G_1") (pintype "bidirectional"))
      (node (ref "R2_EP_DR") (pin "2") (pinfunction "2_2") (pintype "bidirectional"))
    )
    (net (code "21") (name "GND") (class "Default")
      (node (ref "C1") (pin "2") (pinfunction "2_2") (pintype "passive"))
      (node (ref "C10") (pin "2") (pinfunction "2_2") (pintype "passive"))
      (node (ref "C11") (pin "2") (pinfunction "2_2") (pintype "passive"))
      (node (ref "C12") (pin "2") (pinfunction "2_2") (pintype "passive"))
      (node (ref "C13") (pin "2") (pinfunction "2_2") (pintype "passive"))
      (node (ref "C14") (pin "2") (pinfunction "2_2") (pintype "passive"))
      (node (ref "C15") (pin "2") (pinfunction "2_2") (pintype "passive"))
      (node (ref "C16") (pin "2") (pinfunction "2_2") (pintype "passive"))
      (node (ref "C17") (pin "2") (pinfunction "2_2") (pintype "passive"))
      (node (ref "C18") (pin "2") (pinfunction "2_2") (pintype "passive"))
      (node (ref "C19") (pin "1") (pinfunction "1_1") (pintype "passive"))
      (node (ref "C1_EP_DR") (pin "2") (pinfunction "2_2") (pintype "passive"))
      (node (ref "C2") (pin "2") (pinfunction "2_2") (pintype "passive"))
      (node (ref "C20") (pin "2") (pinfunction "2_2") (pintype "passive"))
      (node (ref "C21") (pin "2") (pinfunction "2_2") (pintype "passive"))
      (node (ref "C22") (pin "2") (pinfunction "2_2") (pintype "passive"))
      (node (ref "C23") (pin "1") (pinfunction "1_1") (pintype "passive"))
      (node (ref "C24") (pin "1") (pinfunction "1_1") (pintype "passive"))
      (node (ref "C25") (pin "2") (pinfunction "2_2") (pintype "passive"))
      (node (ref "C27") (pin "1") (pinfunction "1_1") (pintype "passive"))
      (node (ref "C29") (pin "1") (pinfunction "1_1") (pintype "passive"))
      (node (ref "C3") (pin "2") (pinfunction "2_2") (pintype "passive"))
      (node (ref "C30") (pin "1") (pinfunction "1_1") (pintype "passive"))
      (node (ref "C31") (pin "1") (pinfunction "1_1") (pintype "passive"))
      (node (ref "C32") (pin "1") (pinfunction "1_1") (pintype "passive"))
      (node (ref "C33") (pin "2") (pinfunction "2_2") (pintype "passive"))
      (node (ref "C34") (pin "1") (pinfunction "1_1") (pintype "passive"))
      (node (ref "C37") (pin "1") (pinfunction "1_1") (pintype "passive"))
      (node (ref "C38") (pin "1") (pinfunction "1_1") (pintype "passive"))
      (node (ref "C39") (pin "2") (pinfunction "2_2") (pintype "passive"))
      (node (ref "C4") (pin "2") (pinfunction "2_2") (pintype "passive"))
      (node (ref "C42") (pin "2") (pinfunction "2_2") (pintype "passive"))
      (node (ref "C43") (pin "2") (pinfunction "2_2") (pintype "passive"))
      (node (ref "C5") (pin "2") (pinfunction "2_2") (pintype "passive"))
      (node (ref "C6") (pin "2") (pinfunction "2_2") (pintype "passive"))
      (node (ref "C7") (pin "2") (pinfunction "2_2") (pintype "passive"))
      (node (ref "C8") (pin "2") (pinfunction "2_2") (pintype "passive"))
      (node (ref "C9") (pin "2") (pinfunction "2_2") (pintype "passive"))
      (node (ref "D3") (pin "2") (pinfunction "GND_2") (pintype "bidirectional"))
      (node (ref "D4") (pin "2") (pinfunction "A_2") (pintype "bidirectional"))
      (node (ref "EPD_C1") (pin "2") (pinfunction "2_2") (pintype "passive"))
      (node (ref "EPD_C10") (pin "2") (pinfunction "2_2") (pintype "passive"))
      (node (ref "EPD_C11") (pin "2") (pinfunction "2_2") (pintype "passive"))
      (node (ref "EPD_C12") (pin "2") (pinfunction "2_2") (pintype "passive"))
      (node (ref "EPD_C2") (pin "2") (pinfunction "2_2") (pintype "passive"))
      (node (ref "EPD_C5") (pin "2") (pinfunction "2_2") (pintype "passive"))
      (node (ref "EPD_C6") (pin "2") (pinfunction "2_2") (pintype "passive"))
      (node (ref "EPD_C7") (pin "2") (pinfunction "2_2") (pintype "passive"))
      (node (ref "EPD_C8") (pin "2") (pinfunction "2_2") (pintype "passive"))
      (node (ref "EPD_C9") (pin "2") (pinfunction "2_2") (pintype "passive"))
      (node (ref "IC1") (pin "D2") (pinfunction "GND_D2") (pintype "bidirectional"))
      (node (ref "IC2") (pin "B1") (pinfunction "IN/TRIG_B1") (pintype "bidirectional"))
      (node (ref "IC2") (pin "B3") (pinfunction "GND_B3") (pintype "bidirectional"))
      (node (ref "IC3") (pin "8") (pinfunction "GNDIO_8") (pintype "bidirectional"))
      (node (ref "IC3") (pin "9") (pinfunction "GND_9") (pintype "bidirectional"))
      (node (ref "IC9") (pin "B1") (pinfunction "VSEL_B1") (pintype "bidirectional"))
      (node (ref "IC9") (pin "C1") (pinfunction "AGND_C1") (pintype "bidirectional"))
      (node (ref "IC9") (pin "C2") (pinfunction "PGND_1_C2") (pintype "bidirectional"))
      (node (ref "IC9") (pin "C3") (pinfunction "PGND_2_C3") (pintype "bidirectional"))
      (node (ref "J1") (pin "17") (pinfunction "17_17") (pintype "bidirectional"))
      (node (ref "J1") (pin "8") (pinfunction "8_8") (pintype "bidirectional"))
      (node (ref "J1") (pin "MP1") (pinfunction "MP1_MP1") (pintype "bidirectional"))
      (node (ref "J1") (pin "MP2") (pinfunction "MP2_MP2") (pintype "bidirectional"))
      (node (ref "J2") (pin "3") (pinfunction "3_3") (pintype "bidirectional"))
      (node (ref "J2") (pin "5") (pinfunction "5_5") (pintype "bidirectional"))
      (node (ref "J4") (pin "A12_B1") (pinfunction "GND_A12_B1") (pintype "power_in"))
      (node (ref "J4") (pin "A1_B12") (pinfunction "GND_A1_B12") (pintype "power_in"))
      (node (ref "J4") (pin "SH1") (pinfunction "SHIELD_SH1") (pintype "passive"))
      (node (ref "J4") (pin "SH2") (pinfunction "SHIELD_SH2") (pintype "passive"))
      (node (ref "J4") (pin "SH3") (pinfunction "SHIELD_SH3") (pintype "passive"))
      (node (ref "J4") (pin "SH4") (pinfunction "SHIELD_SH4") (pintype "passive"))
      (node (ref "R1_USB") (pin "1") (pinfunction "1_1") (pintype "bidirectional"))
      (node (ref "R2_EP_DR") (pin "1") (pinfunction "1_1") (pintype "bidirectional"))
      (node (ref "R2_USB") (pin "2") (pinfunction "2_2") (pintype "bidirectional"))
      (node (ref "R3") (pin "2") (pinfunction "2_2") (pintype "bidirectional"))
      (node (ref "R9") (pin "1") (pinfunction "1_1") (pintype "bidirectional"))
      (node (ref "R_TYPE_SEL") (pin "1") (pinfunction "1_1") (pintype "bidirectional"))
      (node (ref "SJ1") (pin "1") (pinfunction "1_1") (pintype "passive"))
      (node (ref "SW_DN") (pin "1") (pinfunction "1_1") (pintype "passive"))
      (node (ref "SW_ENT") (pin "1") (pinfunction "1_1") (pintype "passive"))
      (node (ref "SW_UP") (pin "1") (pinfunction "1_1") (pintype "passive"))
      (node (ref "TP_BAT_GND") (pin "TP") (pinfunction "TP_TP") (pintype "input"))
      (node (ref "TP_GND") (pin "TP") (pinfunction "TP_TP") (pintype "input"))
      (node (ref "U1") (pin "P$74") (pinfunction "VSS_PAD_P$74") (pintype "bidirectional"))
      (node (ref "U1") (pin "P$75") (pinfunction "VSS_PAD_P$75") (pintype "bidirectional"))
      (node (ref "U1") (pin "P$76") (pinfunction "VSS_PAD_P$76") (pintype "bidirectional"))
      (node (ref "U1") (pin "P$77") (pinfunction "VSS_PAD_P$77") (pintype "bidirectional"))
      (node (ref "U1") (pin "P$78") (pinfunction "VSS_PAD_P$78") (pintype "bidirectional"))
      (node (ref "U1") (pin "P$79") (pinfunction "VSS_PAD_P$79") (pintype "bidirectional"))
      (node (ref "U1") (pin "P$80") (pinfunction "VSS_PAD_P$80") (pintype "bidirectional"))
      (node (ref "U1") (pin "P$81") (pinfunction "VSS_PAD_P$81") (pintype "bidirectional"))
      (node (ref "U1") (pin "P$82") (pinfunction "VSS_PAD_P$82") (pintype "bidirectional"))
      (node (ref "U1") (pin "P$83") (pinfunction "VSS_PAD_P$83") (pintype "bidirectional"))
      (node (ref "U1") (pin "P$84") (pinfunction "VSS_PAD_P$84") (pintype "bidirectional"))
      (node (ref "U1") (pin "P$85") (pinfunction "VSS_PAD_P$85") (pintype "bidirectional"))
      (node (ref "U1") (pin "P$86") (pinfunction "VSS_PAD_P$86") (pintype "bidirectional"))
      (node (ref "U1") (pin "P$87") (pinfunction "VSS_PAD_P$87") (pintype "bidirectional"))
      (node (ref "U1") (pin "P$88") (pinfunction "VSS_PAD_P$88") (pintype "bidirectional"))
      (node (ref "U1") (pin "P$89") (pinfunction "VSS_PAD_P$89") (pintype "bidirectional"))
      (node (ref "U1") (pin "P$90") (pinfunction "VSS_PAD_P$90") (pintype "bidirectional"))
      (node (ref "U1") (pin "P$B7") (pinfunction "VSS_P$B7") (pintype "power_in"))
      (node (ref "U1") (pin "P$F23") (pinfunction "VSS_PA_P$F23") (pintype "bidirectional"))
      (node (ref "U3") (pin "1") (pinfunction "CTG_1") (pintype "power_in"))
      (node (ref "U3") (pin "4") (pinfunction "GND_4") (pintype "power_in"))
      (node (ref "U3") (pin "6") (pinfunction "QSTRT_6") (pintype "input"))
      (node (ref "U3") (pin "9") (pinfunction "EP_9") (pintype "power_in"))
      (node (ref "X1") (pin "2") (pinfunction "2_2") (pintype "passive"))
      (node (ref "X1") (pin "4") (pinfunction "4_4") (pintype "passive"))
    )
    (net (code "22") (name "HAPTIC_EN{slash}1.4C") (class "Default")
      (node (ref "IC2") (pin "A1") (pinfunction "EN_A1") (pintype "bidirectional"))
    )
    (net (code "23") (name "HAPTIC_EN{slash}2.6A") (class "Default")
      (node (ref "U1") (pin "P$U1") (pinfunction "P0.12_P$U1") (pintype "bidirectional"))
    )
    (net (code "24") (name "IMU_INT1") (class "Default")
      (node (ref "IC3") (pin "5") (pinfunction "INT1_5") (pintype "bidirectional"))
      (node (ref "U1") (pin "P$N1") (pinfunction "P0.08_P$N1") (pintype "bidirectional"))
    )
    (net (code "25") (name "IMU_INT2") (class "Default")
      (node (ref "IC3") (pin "6") (pinfunction "INT2_6") (pintype "bidirectional"))
      (node (ref "U1") (pin "P$P2") (pinfunction "P1.08_P$P2") (pintype "bidirectional"))
    )
    (net (code "26") (name "LX1") (class "Default")
      (node (ref "IC9") (pin "B2") (pinfunction "SW1_1_B2") (pintype "bidirectional"))
      (node (ref "IC9") (pin "B3") (pinfunction "SW1_2_B3") (pintype "bidirectional"))
      (node (ref "L7") (pin "1") (pinfunction "1_1") (pintype "bidirectional"))
    )
    (net (code "27") (name "LX2") (class "Default")
      (node (ref "IC9") (pin "D2") (pinfunction "SW2_1_D2") (pintype "bidirectional"))
      (node (ref "IC9") (pin "D3") (pinfunction "SW2_2_D3") (pintype "bidirectional"))
      (node (ref "L7") (pin "2") (pinfunction "2_2") (pintype "bidirectional"))
    )
    (net (code "28") (name "MOSI{slash}1.5B") (class "Default")
      (node (ref "J1") (pin "14") (pinfunction "14_14") (pintype "bidirectional"))
    )
    (net (code "29") (name "MOSI{slash}2.2D") (class "Default")
      (node (ref "U1") (pin "P$B13") (pinfunction "P0.03/AIN1_P$B13") (pintype "bidirectional"))
    )
    (net (code "30") (name "Net-(ANT1-FEED)") (class "Default")
      (node (ref "ANT1") (pin "1") (pinfunction "FEED_1") (pintype "input"))
      (node (ref "C22") (pin "1") (pinfunction "1_1") (pintype "passive"))
      (node (ref "C4") (pin "1") (pinfunction "1_1") (pintype "passive"))
      (node (ref "L1") (pin "2") (pinfunction "2_2") (pintype "passive"))
    )
    (net (code "31") (name "Net-(D2-K)") (class "Default")
      (node (ref "C2-EP-DR") (pin "1") (pinfunction "1_1") (pintype "passive"))
      (node (ref "D2") (pin "1") (pinfunction "K_1") (pintype "bidirectional"))
      (node (ref "D4") (pin "1") (pinfunction "K_1") (pintype "bidirectional"))
    )
    (net (code "32") (name "Net-(D5-A)") (class "Default")
      (node (ref "C2-EP-DR") (pin "2") (pinfunction "2_2") (pintype "passive"))
      (node (ref "D5") (pin "2") (pinfunction "A_2") (pintype "bidirectional"))
      (node (ref "L5") (pin "1") (pinfunction "1_1") (pintype "passive"))
      (node (ref "Q3") (pin "3") (pinfunction "D_3") (pintype "bidirectional"))
    )
    (net (code "33") (name "Net-(EPD_C1-Pad1)") (class "Default")
      (node (ref "EPD_C1") (pin "1") (pinfunction "1_1") (pintype "passive"))
      (node (ref "J1") (pin "5") (pinfunction "5_5") (pintype "bidirectional"))
    )
    (net (code "34") (name "Net-(EPD_C2-Pad1)") (class "Default")
      (node (ref "EPD_C2") (pin "1") (pinfunction "1_1") (pintype "passive"))
      (node (ref "J1") (pin "4") (pinfunction "4_4") (pintype "bidirectional"))
    )
    (net (code "35") (name "Net-(EPD_C6-Pad1)") (class "Default")
      (node (ref "EPD_C6") (pin "1") (pinfunction "1_1") (pintype "passive"))
      (node (ref "J1") (pin "18") (pinfunction "18_18") (pintype "bidirectional"))
    )
    (net (code "36") (name "Net-(EPD_C7-Pad1)") (class "Default")
      (node (ref "EPD_C7") (pin "1") (pinfunction "1_1") (pintype "passive"))
      (node (ref "J1") (pin "19") (pinfunction "19_19") (pintype "bidirectional"))
    )
    (net (code "37") (name "Net-(EPD_C8-Pad1)") (class "Default")
      (node (ref "EPD_C8") (pin "1") (pinfunction "1_1") (pintype "passive"))
      (node (ref "J1") (pin "20") (pinfunction "20_20") (pintype "bidirectional"))
    )
    (net (code "38") (name "Net-(EPD_C10-Pad1)") (class "Default")
      (node (ref "EPD_C10") (pin "1") (pinfunction "1_1") (pintype "passive"))
      (node (ref "J1") (pin "22") (pinfunction "22_22") (pintype "bidirectional"))
    )
    (net (code "39") (name "Net-(EPD_C12-Pad1)") (class "Default")
      (node (ref "EPD_C12") (pin "1") (pinfunction "1_1") (pintype "passive"))
      (node (ref "J1") (pin "24") (pinfunction "24_24") (pintype "bidirectional"))
    )
    (net (code "40") (name "Net-(IC1-TS{slash}MR)") (class "Default")
      (node (ref "IC1") (pin "D1") (pinfunction "TS/MR_D1") (pintype "bidirectional"))
      (node (ref "R9") (pin "2") (pinfunction "2_2") (pintype "bidirectional"))
    )
    (net (code "41") (name "Net-(IC2-REG)") (class "Default")
      (node (ref "C32") (pin "2") (pinfunction "2_2") (pintype "passive"))
      (node (ref "IC2") (pin "A2") (pinfunction "REG_A2") (pintype "bidirectional"))
    )
    (net (code "42") (name "Net-(IC3-SDO)") (class "Default")
      (node (ref "IC3") (pin "1") (pinfunction "SDO_1") (pintype "bidirectional"))
      (node (ref "R3") (pin "1") (pinfunction "1_1") (pintype "bidirectional"))
    )
    (net (code "43") (name "Net-(IC9-SCL)") (class "Default")
      (node (ref "IC9") (pin "D1") (pinfunction "SCL_D1") (pintype "bidirectional"))
      (node (ref "R4") (pin "2") (pinfunction "2_2") (pintype "bidirectional"))
    )
    (net (code "44") (name "Net-(IC9-SDA)") (class "Default")
      (node (ref "IC9") (pin "E1") (pinfunction "SDA_E1") (pintype "bidirectional"))
      (node (ref "R2") (pin "2") (pinfunction "2_2") (pintype "bidirectional"))
    )
    (net (code "45") (name "Net-(J4-CC1)") (class "Default")
      (node (ref "J4") (pin "A5") (pinfunction "CC1_A5") (pintype "bidirectional"))
      (node (ref "R1_USB") (pin "2") (pinfunction "2_2") (pintype "bidirectional"))
    )
    (net (code "46") (name "Net-(J4-CC2)") (class "Default")
      (node (ref "J4") (pin "B5") (pinfunction "CC2_B5") (pintype "bidirectional"))
      (node (ref "R2_USB") (pin "1") (pinfunction "1_1") (pintype "bidirectional"))
    )
    (net (code "47") (name "Net-(L2-Pad1)") (class "Default")
      (node (ref "L2") (pin "1") (pinfunction "1_1") (pintype "passive"))
      (node (ref "L3") (pin "2") (pinfunction "2_2") (pintype "passive"))
    )
    (net (code "48") (name "Net-(R1_EP_DR-Pad1)") (class "Default")
      (node (ref "R1_EP_DR") (pin "1") (pinfunction "1_1") (pintype "bidirectional"))
      (node (ref "R_TYPE_SEL") (pin "2") (pinfunction "2_2") (pintype "bidirectional"))
      (node (ref "SJ1") (pin "2") (pinfunction "2_2") (pintype "passive"))
    )
    (net (code "49") (name "Net-(U1-ANT)") (class "Default")
      (node (ref "C3") (pin "1") (pinfunction "1_1") (pintype "passive"))
      (node (ref "L1") (pin "1") (pinfunction "1_1") (pintype "passive"))
      (node (ref "U1") (pin "P$H23") (pinfunction "ANT_P$H23") (pintype "bidirectional"))
    )
    (net (code "50") (name "Net-(U1-DCC)") (class "Default")
      (node (ref "L3") (pin "1") (pinfunction "1_1") (pintype "passive"))
      (node (ref "U1") (pin "P$B3") (pinfunction "DCC_P$B3") (pintype "output"))
    )
    (net (code "51") (name "Net-(U1-DEC1)") (class "Default")
      (node (ref "C5") (pin "1") (pinfunction "1_1") (pintype "passive"))
      (node (ref "U1") (pin "P$C1") (pinfunction "DEC1_P$C1") (pintype "power_in"))
    )
    (net (code "52") (name "Net-(U1-DEC2)") (class "Default")
      (node (ref "C13") (pin "1") (pinfunction "1_1") (pintype "passive"))
      (node (ref "U1") (pin "P$A18") (pinfunction "DEC2_P$A18") (pintype "bidirectional"))
    )
    (net (code "53") (name "Net-(U1-DEC3)") (class "Default")
      (node (ref "C11") (pin "1") (pinfunction "1_1") (pintype "passive"))
      (node (ref "U1") (pin "P$D23") (pinfunction "DEC3_P$D23") (pintype "bidirectional"))
    )
    (net (code "54") (name "Net-(U1-DEC3V3)") (class "Default")
      (node (ref "C20") (pin "1") (pinfunction "1_1") (pintype "passive"))
      (node (ref "U1") (pin "P$AC5") (pinfunction "DEC3V3_P$AC5") (pintype "bidirectional"))
    )
    (net (code "55") (name "Net-(U1-DEC4)") (class "Default")
      (node (ref "C10") (pin "1") (pinfunction "1_1") (pintype "passive"))
      (node (ref "C15") (pin "1") (pinfunction "1_1") (pintype "passive"))
      (node (ref "C16") (pin "1") (pinfunction "1_1") (pintype "passive"))
      (node (ref "L2") (pin "2") (pinfunction "2_2") (pintype "passive"))
      (node (ref "U1") (pin "P$B5") (pinfunction "DEC4_P$B5") (pintype "power_in"))
      (node (ref "U1") (pin "P$E24") (pinfunction "DEC6_P$E24") (pintype "bidirectional"))
    )
    (net (code "56") (name "Net-(U1-DEC5)") (class "Default")
      (node (ref "C9") (pin "1") (pinfunction "1_1") (pintype "passive"))
      (node (ref "U1") (pin "P$N24") (pinfunction "DEC5_P$N24") (pintype "bidirectional"))
    )
    (net (code "57") (name "Net-(U1-P0.00{slash}XL1)") (class "Default")
      (node (ref "C17") (pin "1") (pinfunction "1_1") (pintype "passive"))
      (node (ref "U1") (pin "P$D2") (pinfunction "P0.00/XL1_P$D2") (pintype "bidirectional"))
      (node (ref "X2") (pin "1") (pinfunction "1_1") (pintype "passive"))
    )
    (net (code "58") (name "Net-(U1-P0.01{slash}XL2)") (class "Default")
      (node (ref "C18") (pin "1") (pinfunction "1_1") (pintype "passive"))
      (node (ref "U1") (pin "P$F2") (pinfunction "P0.01/XL2_P$F2") (pintype "bidirectional"))
      (node (ref "X2") (pin "2") (pinfunction "2_2") (pintype "passive"))
    )
    (net (code "59") (name "Net-(U1-XC1)") (class "Default")
      (node (ref "C1") (pin "1") (pinfunction "1_1") (pintype "passive"))
      (node (ref "U1") (pin "P$B24") (pinfunction "XC1_P$B24") (pintype "input"))
      (node (ref "X1") (pin "1") (pinfunction "1_1") (pintype "passive"))
    )
    (net (code "60") (name "Net-(U1-XC2)") (class "Default")
      (node (ref "C2") (pin "1") (pinfunction "1_1") (pintype "passive"))
      (node (ref "U1") (pin "P$A23") (pinfunction "XC2_P$A23") (pintype "output"))
      (node (ref "X1") (pin "3") (pinfunction "3_3") (pintype "passive"))
    )
    (net (code "61") (name "OUT+") (class "Default")
      (node (ref "IC2") (pin "A3") (pinfunction "OUT+_A3") (pintype "bidirectional"))
      (node (ref "TP_OP") (pin "TP") (pinfunction "TP_TP") (pintype "input"))
    )
    (net (code "62") (name "OUT-") (class "Default")
      (node (ref "IC2") (pin "C3") (pinfunction "OUT-_C3") (pintype "bidirectional"))
      (node (ref "TP_ON") (pin "TP") (pinfunction "TP_TP") (pintype "input"))
    )
    (net (code "63") (name "P0.04") (class "Default")
      (node (ref "U1") (pin "P$J1") (pinfunction "P0.04/AIN2_P$J1") (pintype "bidirectional"))
    )
    (net (code "64") (name "P0.09") (class "Default")
      (node (ref "U1") (pin "P$L24") (pinfunction "P0.09/NFC1_P$L24") (pintype "bidirectional"))
    )
    (net (code "65") (name "P0.13{slash}1.5D") (class "Default")
      (node (ref "C30") (pin "2") (pinfunction "2_2") (pintype "passive"))
      (node (ref "R5") (pin "1") (pinfunction "1_1") (pintype "bidirectional"))
      (node (ref "SW_UP") (pin "2") (pinfunction "2_2") (pintype "passive"))
    )
    (net (code "66") (name "P0.13{slash}2.6C") (class "Default")
      (node (ref "U1") (pin "P$AD8") (pinfunction "P0.13_P$AD8") (pintype "bidirectional"))
    )
    (net (code "67") (name "P0.14{slash}1.5D") (class "Default")
      (node (ref "C31") (pin "2") (pinfunction "2_2") (pintype "passive"))
      (node (ref "R8") (pin "1") (pinfunction "1_1") (pintype "bidirectional"))
      (node (ref "SW_ENT") (pin "2") (pinfunction "2_2") (pintype "passive"))
    )
    (net (code "68") (name "P0.14{slash}2.7C") (class "Default")
      (node (ref "U1") (pin "P$AC9") (pinfunction "P0.14_P$AC9") (pintype "bidirectional"))
    )
    (net (code "69") (name "P0.19") (class "Default")
      (node (ref "U1") (pin "P$AC15") (pinfunction "P0.19_P$AC15") (pintype "bidirectional"))
    )
    (net (code "70") (name "P0.20") (class "Default")
      (node (ref "U1") (pin "P$AD16") (pinfunction "P0.20_P$AD16") (pintype "bidirectional"))
    )
    (net (code "71") (name "P0.21") (class "Default")
      (node (ref "U1") (pin "P$AC17") (pinfunction "P0.21_P$AC17") (pintype "bidirectional"))
    )
    (net (code "72") (name "P0.22") (class "Default")
      (node (ref "U1") (pin "P$AD18") (pinfunction "P0.22_P$AD18") (pintype "bidirectional"))
    )
    (net (code "73") (name "P0.23") (class "Default")
      (node (ref "U1") (pin "P$AC19") (pinfunction "P0.23_P$AC19") (pintype "bidirectional"))
    )
    (net (code "74") (name "P0.24") (class "Default")
      (node (ref "U1") (pin "P$AD20") (pinfunction "P0.24_P$AD20") (pintype "bidirectional"))
    )
    (net (code "75") (name "P0.25") (class "Default")
      (node (ref "U1") (pin "P$AC21") (pinfunction "P0.25_P$AC21") (pintype "bidirectional"))
    )
    (net (code "76") (name "P0.26") (class "Default")
      (node (ref "U1") (pin "P$G1") (pinfunction "P0.26_P$G1") (pintype "bidirectional"))
    )
    (net (code "77") (name "P0.27") (class "Default")
      (node (ref "U1") (pin "P$H2") (pinfunction "P0.27_P$H2") (pintype "bidirectional"))
    )
    (net (code "78") (name "P0.28") (class "Default")
      (node (ref "U1") (pin "P$B11") (pinfunction "P0.28/AIN4_P$B11") (pintype "bidirectional"))
    )
    (net (code "79") (name "P0.29") (class "Default")
      (node (ref "U1") (pin "P$A10") (pinfunction "P0.29/AIN5_P$A10") (pintype "bidirectional"))
    )
    (net (code "80") (name "P0.30") (class "Default")
      (node (ref "U1") (pin "P$B9") (pinfunction "P0.30/AIN6_P$B9") (pintype "bidirectional"))
    )
    (net (code "81") (name "P0.31") (class "Default")
      (node (ref "U1") (pin "P$A8") (pinfunction "P0.31/AIN7_P$A8") (pintype "bidirectional"))
    )
    (net (code "82") (name "P1.01") (class "Default")
      (node (ref "U1") (pin "P$Y23") (pinfunction "P1.01_P$Y23") (pintype "bidirectional"))
    )
    (net (code "83") (name "P1.01{slash}1.6C") (class "Default")
      (node (ref "Q1") (pin "1") (pinfunction "G_1") (pintype "bidirectional"))
      (node (ref "R_PWR_EPD") (pin "1") (pinfunction "1_1") (pintype "bidirectional"))
    )
    (net (code "84") (name "P1.02{slash}1.6C") (class "Default")
      (node (ref "C29") (pin "2") (pinfunction "2_2") (pintype "passive"))
      (node (ref "R7") (pin "1") (pinfunction "1_1") (pintype "bidirectional"))
      (node (ref "SW_DN") (pin "2") (pinfunction "2_2") (pintype "passive"))
    )
    (net (code "85") (name "P1.02{slash}2.8C") (class "Default")
      (node (ref "U1") (pin "P$W24") (pinfunction "P1.02_P$W24") (pintype "bidirectional"))
    )
    (net (code "86") (name "P1.03") (class "Default")
      (node (ref "U1") (pin "P$V23") (pinfunction "P1.03_P$V23") (pintype "bidirectional"))
    )
    (net (code "87") (name "P1.04") (class "Default")
      (node (ref "U1") (pin "P$U24") (pinfunction "P1.04_P$U24") (pintype "bidirectional"))
    )
    (net (code "88") (name "P1.05") (class "Default")
      (node (ref "U1") (pin "P$T23") (pinfunction "P1.05_P$T23") (pintype "bidirectional"))
    )
    (net (code "89") (name "P1.06") (class "Default")
      (node (ref "U1") (pin "P$R24") (pinfunction "P1.06_P$R24") (pintype "bidirectional"))
    )
    (net (code "90") (name "P1.07") (class "Default")
      (node (ref "U1") (pin "P$P23") (pinfunction "P1.07_P$P23") (pintype "bidirectional"))
    )
    (net (code "91") (name "P1.09") (class "Default")
      (node (ref "U1") (pin "P$R1") (pinfunction "P1.09_P$R1") (pintype "bidirectional"))
    )
    (net (code "92") (name "P1.10") (class "Default")
      (node (ref "U1") (pin "P$A20") (pinfunction "P1.10_P$A20") (pintype "bidirectional"))
    )
    (net (code "93") (name "P1.11") (class "Default")
      (node (ref "U1") (pin "P$B19") (pinfunction "P1.11_P$B19") (pintype "bidirectional"))
    )
    (net (code "94") (name "P1.12") (class "Default")
      (node (ref "U1") (pin "P$B17") (pinfunction "P1.12_P$B17") (pintype "bidirectional"))
    )
    (net (code "95") (name "P1.13") (class "Default")
      (node (ref "U1") (pin "P$A16") (pinfunction "P1.13_P$A16") (pintype "bidirectional"))
    )
    (net (code "96") (name "P1.14") (class "Default")
      (node (ref "U1") (pin "P$B15") (pinfunction "P1.14_P$B15") (pintype "bidirectional"))
    )
    (net (code "97") (name "P1.15") (class "Default")
      (node (ref "U1") (pin "P$A14") (pinfunction "P1.15_P$A14") (pintype "bidirectional"))
    )
    (net (code "98") (name "PMIC_INT") (class "Default")
      (node (ref "IC1") (pin "A1") (pinfunction "~{INT}_A1") (pintype "bidirectional"))
      (node (ref "U1") (pin "P$T2") (pinfunction "P0.11_P$T2") (pintype "bidirectional"))
    )
    (net (code "99") (name "PREVGH") (class "Default")
      (node (ref "D5") (pin "1") (pinfunction "K_1") (pintype "bidirectional"))
      (node (ref "EPD_C9") (pin "1") (pinfunction "1_1") (pintype "passive"))
      (node (ref "J1") (pin "21") (pinfunction "21_21") (pintype "bidirectional"))
    )
    (net (code "100") (name "PREVGL") (class "Default")
      (node (ref "D2") (pin "2") (pinfunction "A_2") (pintype "bidirectional"))
      (node (ref "EPD_C11") (pin "1") (pinfunction "1_1") (pintype "passive"))
      (node (ref "J1") (pin "23") (pinfunction "23_23") (pintype "bidirectional"))
    )
    (net (code "101") (name "RESE") (class "Default")
      (node (ref "J1") (pin "3") (pinfunction "3_3") (pintype "bidirectional"))
      (node (ref "Q3") (pin "2") (pinfunction "S_2") (pintype "bidirectional"))
      (node (ref "R1_EP_DR") (pin "2") (pinfunction "2_2") (pintype "bidirectional"))
    )
    (net (code "102") (name "RESET") (class "Default")
      (node (ref "J2") (pin "6") (pinfunction "6_6") (pintype "bidirectional"))
      (node (ref "TP_RESET") (pin "TP") (pinfunction "TP_TP") (pintype "input"))
      (node (ref "U1") (pin "P$AC13") (pinfunction "P0.18/RESET_P$AC13") (pintype "bidirectional"))
    )
    (net (code "103") (name "SCK{slash}1.5B") (class "Default")
      (node (ref "J1") (pin "13") (pinfunction "13_13") (pintype "bidirectional"))
    )
    (net (code "104") (name "SCK{slash}2.2D") (class "Default")
      (node (ref "U1") (pin "P$A12") (pinfunction "P0.02/AIN0_P$A12") (pintype "bidirectional"))
    )
    (net (code "105") (name "SCL{slash}1.4C") (class "Default")
      (node (ref "IC2") (pin "C1") (pinfunction "SCL_C1") (pintype "bidirectional"))
      (node (ref "U3") (pin "7") (pinfunction "SCL_7") (pintype "input"))
    )
    (net (code "106") (name "SCL{slash}2.4C") (class "Default")
      (node (ref "IC1") (pin "B1") (pinfunction "SCL_B1") (pintype "bidirectional"))
      (node (ref "IC3") (pin "12") (pinfunction "SCX_12") (pintype "bidirectional"))
      (node (ref "R17") (pin "2") (pinfunction "2_2") (pintype "bidirectional"))
      (node (ref "R4") (pin "1") (pinfunction "1_1") (pintype "bidirectional"))
      (node (ref "TP_SCL") (pin "TP") (pinfunction "TP_TP") (pintype "input"))
      (node (ref "U1") (pin "P$M2") (pinfunction "P0.07_P$M2") (pintype "bidirectional"))
    )
    (net (code "107") (name "SDA{slash}1.4C") (class "Default")
      (node (ref "IC2") (pin "B2") (pinfunction "SDA_B2") (pintype "bidirectional"))
      (node (ref "U3") (pin "8") (pinfunction "SDA_8") (pintype "bidirectional"))
    )
    (net (code "108") (name "SDA{slash}2.4C") (class "Default")
      (node (ref "IC1") (pin "C1") (pinfunction "SDA_C1") (pintype "bidirectional"))
      (node (ref "IC3") (pin "2") (pinfunction "SDX_2") (pintype "bidirectional"))
      (node (ref "R18") (pin "2") (pinfunction "2_2") (pintype "bidirectional"))
      (node (ref "R2") (pin "1") (pinfunction "1_1") (pintype "bidirectional"))
      (node (ref "TP_SDA") (pin "TP") (pinfunction "TP_TP") (pintype "input"))
      (node (ref "U1") (pin "P$L1") (pinfunction "P0.06_P$L1") (pintype "bidirectional"))
    )
    (net (code "109") (name "SWDCLK") (class "Default")
      (node (ref "J2") (pin "4") (pinfunction "4_4") (pintype "bidirectional"))
      (node (ref "TP_SWDCLK") (pin "TP") (pinfunction "TP_TP") (pintype "input"))
      (node (ref "U1") (pin "P$AA24") (pinfunction "SWDCLK_P$AA24") (pintype "input"))
    )
    (net (code "110") (name "SWDIO") (class "Default")
      (node (ref "J2") (pin "2") (pinfunction "2_2") (pintype "bidirectional"))
      (node (ref "TP_SWDIO") (pin "TP") (pinfunction "TP_TP") (pintype "input"))
      (node (ref "U1") (pin "P$AC24") (pinfunction "SWDIO_P$AC24") (pintype "bidirectional"))
    )
    (net (code "111") (name "SWO") (class "Default")
      (node (ref "TP_SWO") (pin "TP") (pinfunction "TP_TP") (pintype "input"))
      (node (ref "U1") (pin "P$AD22") (pinfunction "P1.00_P$AD22") (pintype "bidirectional"))
    )
    (net (code "112") (name "VBAT{slash}1.2A") (class "Default")
      (node (ref "C27") (pin "2") (pinfunction "2_2") (pintype "passive"))
      (node (ref "TP_VBAT") (pin "TP") (pinfunction "TP_TP") (pintype "input"))
      (node (ref "U3") (pin "2") (pinfunction "CELL_2") (pintype "power_in"))
      (node (ref "U3") (pin "3") (pinfunction "VDD_3") (pintype "power_in"))
    )
    (net (code "113") (name "VBAT{slash}2.5C") (class "Default")
      (node (ref "C37") (pin "2") (pinfunction "2_2") (pintype "passive"))
      (node (ref "IC1") (pin "C2") (pinfunction "BAT_C2") (pintype "bidirectional"))
    )
    (net (code "114") (name "VBUS{slash}1.5D") (class "Default")
      (node (ref "C42") (pin "1") (pinfunction "1_1") (pintype "passive"))
      (node (ref "C43") (pin "1") (pinfunction "1_1") (pintype "passive"))
      (node (ref "D3") (pin "5") (pinfunction "VBUS_5") (pintype "bidirectional"))
      (node (ref "J4") (pin "A4_B9") (pinfunction "VBUS_A4_B9") (pintype "power_in"))
      (node (ref "J4") (pin "A9_B4") (pinfunction "VBUS_A9_B4") (pintype "power_in"))
    )
    (net (code "115") (name "VBUS{slash}2.6D") (class "Default")
      (node (ref "C21") (pin "1") (pinfunction "1_1") (pintype "passive"))
      (node (ref "C38") (pin "2") (pinfunction "2_2") (pintype "passive"))
      (node (ref "IC1") (pin "A2") (pinfunction "IN_A2") (pintype "bidirectional"))
      (node (ref "U1") (pin "P$AD2") (pinfunction "VBUS_P$AD2") (pintype "power_in"))
    )
    (net (code "116") (name "VREG") (class "Default")
      (node (ref "C23") (pin "2") (pinfunction "2_2") (pintype "passive"))
      (node (ref "C24") (pin "2") (pinfunction "2_2") (pintype "passive"))
      (node (ref "C39") (pin "1") (pinfunction "1_1") (pintype "passive"))
      (node (ref "IC1") (pin "B2") (pinfunction "SYS_B2") (pintype "bidirectional"))
      (node (ref "IC9") (pin "A1") (pinfunction "EN_A1") (pintype "bidirectional"))
      (node (ref "IC9") (pin "A2") (pinfunction "VIN_1_A2") (pintype "bidirectional"))
      (node (ref "IC9") (pin "A3") (pinfunction "VIN_2_A3") (pintype "bidirectional"))
      (node (ref "TP_VREG") (pin "TP") (pinfunction "TP_TP") (pintype "input"))
    )
    (net (code "117") (name "unconnected-(ANT1-NC-Pad2)") (class "Default")
      (node (ref "ANT1") (pin "2") (pinfunction "NC_2") (pintype "no_connect"))
    )
    (net (code "118") (name "unconnected-(IC3-ASCL-Pad11)") (class "Default")
      (node (ref "IC3") (pin "11") (pinfunction "ASCL_11") (pintype "bidirectional"))
    )
    (net (code "119") (name "unconnected-(IC3-ASDA-Pad4)") (class "Default")
      (node (ref "IC3") (pin "4") (pinfunction "ASDA_4") (pintype "bidirectional"))
    )
    (net (code "120") (name "unconnected-(J1-Pad1)") (class "Default")
      (node (ref "J1") (pin "1") (pinfunction "1_1") (pintype "bidirectional"))
    )
    (net (code "121") (name "unconnected-(J1-Pad6)") (class "Default")
      (node (ref "J1") (pin "6") (pinfunction "6_6") (pintype "bidirectional"))
    )
    (net (code "122") (name "unconnected-(J1-Pad7)") (class "Default")
      (node (ref "J1") (pin "7") (pinfunction "7_7") (pintype "bidirectional"))
    )
    (net (code "123") (name "unconnected-(J4-SBU1-PadA8)") (class "Default")
      (node (ref "J4") (pin "A8") (pinfunction "SBU1_A8") (pintype "bidirectional"))
    )
    (net (code "124") (name "unconnected-(J4-SBU2-PadB8)") (class "Default")
      (node (ref "J4") (pin "B8") (pinfunction "SBU2_B8") (pintype "bidirectional"))
    )
    (net (code "125") (name "unconnected-(U1-DCCH-PadP$AB2)") (class "Default")
      (node (ref "U1") (pin "P$AB2") (pinfunction "DCCH_P$AB2") (pintype "bidirectional"))
    )
  )
)
